# Copy_of_DAP-Peripherals-4.net
KiCad netlist of a schematic drawn in Altium Designer
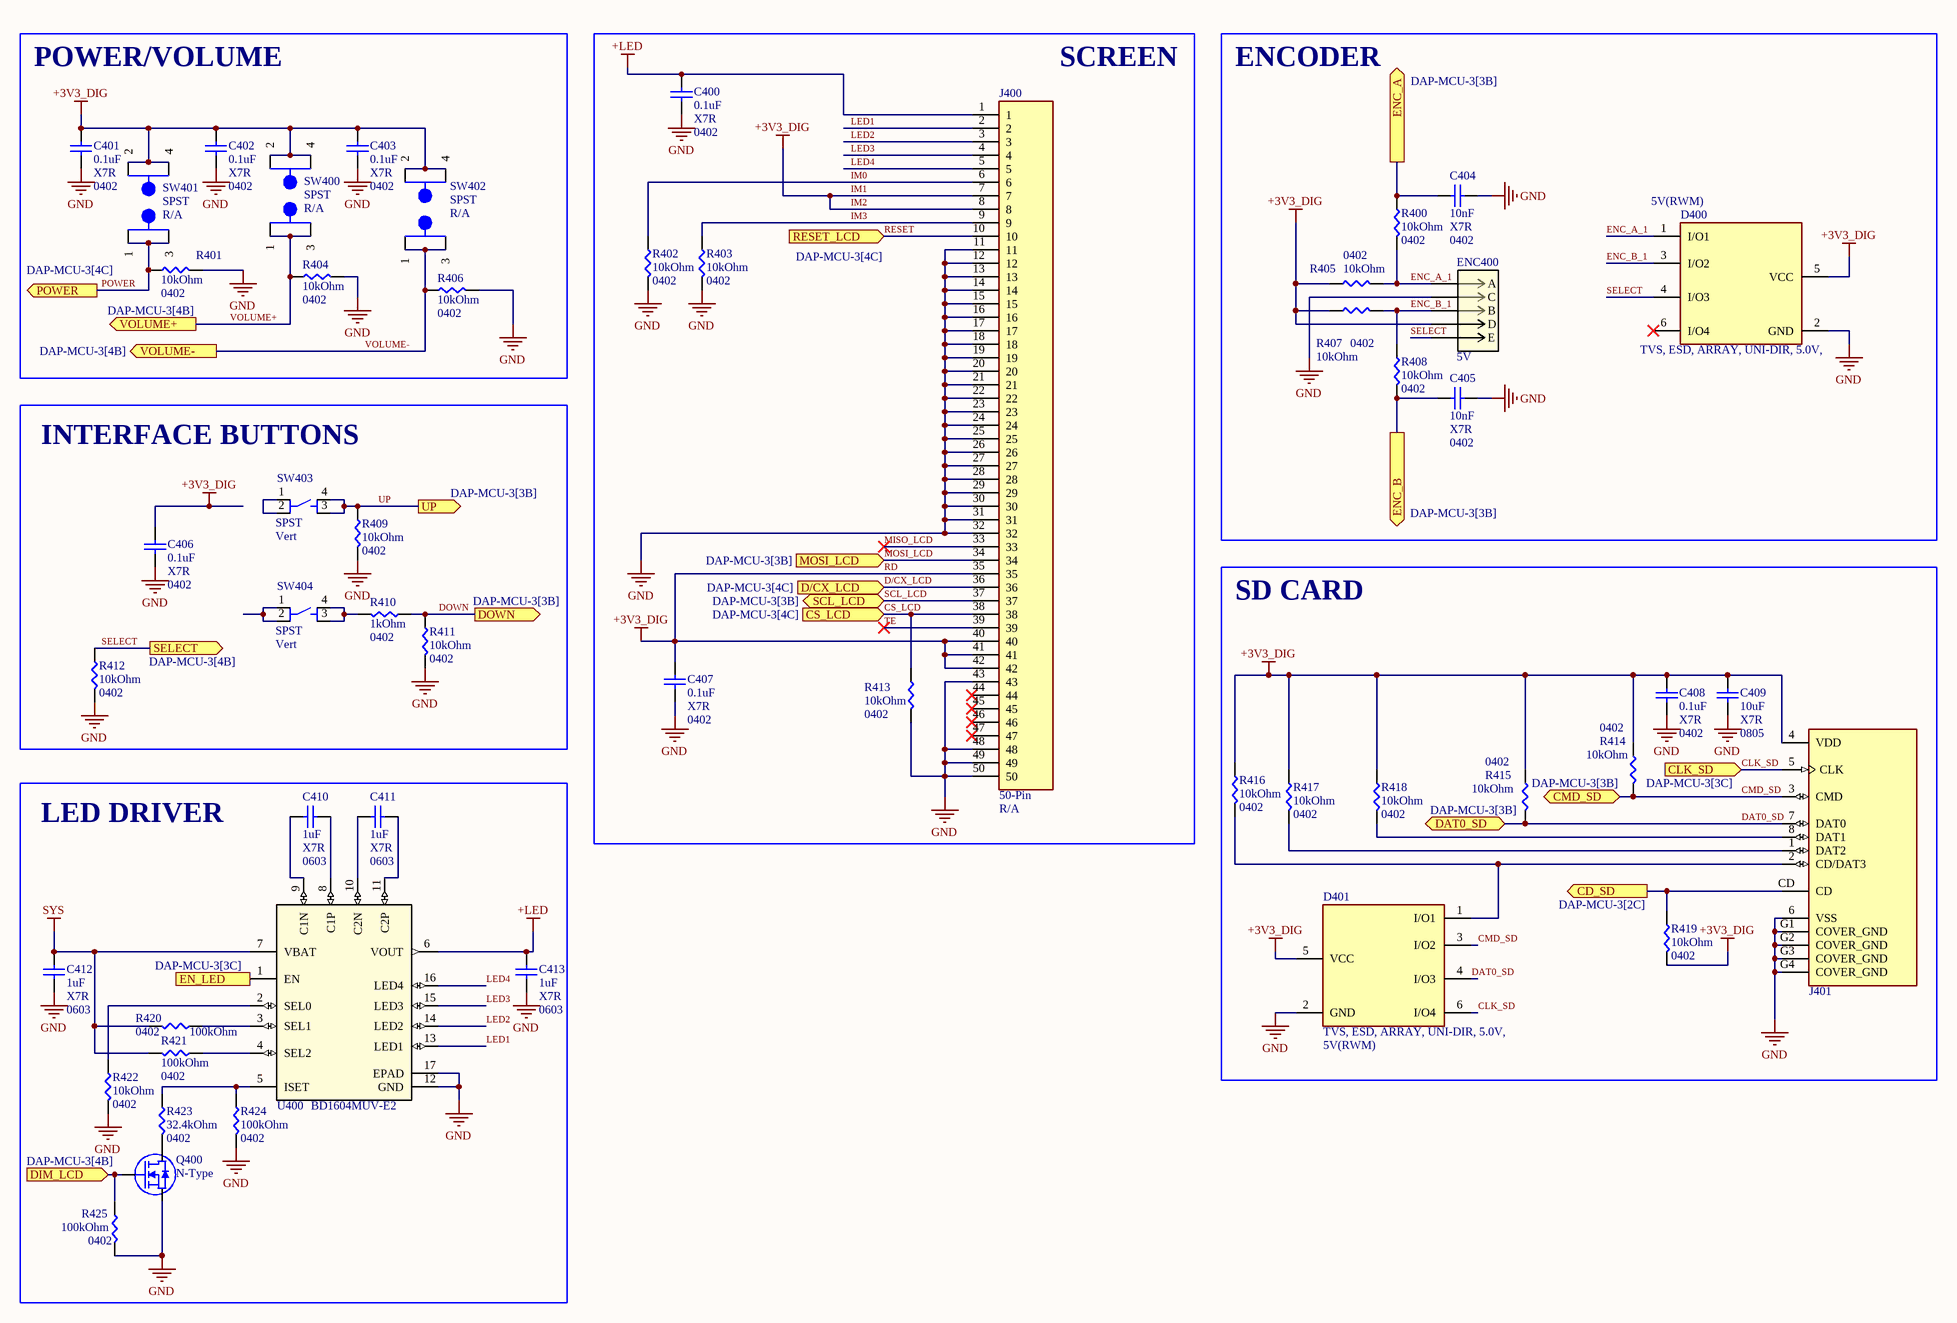
[diagram p0: Copy of DAP-Peripherals-4.SchDoc]

(export (version "E")
  (design (tool "Eeschema 10.0.6"))
  (components
    (comp (ref "C400")
      (value "CAP CER 0.1UF 50V X7R 0402")
      (footprint "CAPC1005X60N")
      (fields
        (field (name "<VALUE>") "0.1uF")
        (field (name "<SPEC>") "X7R")
        (field (name "<FOOTPRINT>") "0402")
        (field (name "CREATOR PROJECT") "DAP")
      )
      (libsource (lib "aloker-Link") (part "CAP"))
    )
    (comp (ref "C401")
      (value "CAP CER 0.1UF 50V X7R 0402")
      (footprint "CAPC1005X60N")
      (fields
        (field (name "<VALUE>") "0.1uF")
        (field (name "<SPEC>") "X7R")
        (field (name "<FOOTPRINT>") "0402")
        (field (name "CREATOR PROJECT") "DAP")
      )
      (libsource (lib "aloker-Link") (part "CAP"))
    )
    (comp (ref "C402")
      (value "CAP CER 0.1UF 50V X7R 0402")
      (footprint "CAPC1005X60N")
      (fields
        (field (name "<VALUE>") "0.1uF")
        (field (name "<SPEC>") "X7R")
        (field (name "<FOOTPRINT>") "0402")
        (field (name "CREATOR PROJECT") "DAP")
      )
      (libsource (lib "aloker-Link") (part "CAP"))
    )
    (comp (ref "C403")
      (value "CAP CER 0.1UF 50V X7R 0402")
      (footprint "CAPC1005X60N")
      (fields
        (field (name "<VALUE>") "0.1uF")
        (field (name "<SPEC>") "X7R")
        (field (name "<FOOTPRINT>") "0402")
        (field (name "CREATOR PROJECT") "DAP")
      )
      (libsource (lib "aloker-Link") (part "CAP"))
    )
    (comp (ref "C404")
      (value "CAP CER 10000PF 16V X7R 0402")
      (footprint "CAPC1005X55N")
      (fields
        (field (name "<VALUE>") "10nF")
        (field (name "<SPEC>") "X7R")
        (field (name "<FOOTPRINT>") "0402")
        (field (name "CREATOR PROJECT") "aRTy")
      )
      (libsource (lib "aloker-Link") (part "CAP"))
    )
    (comp (ref "C405")
      (value "CAP CER 10000PF 16V X7R 0402")
      (footprint "CAPC1005X55N")
      (fields
        (field (name "<VALUE>") "10nF")
        (field (name "<SPEC>") "X7R")
        (field (name "<FOOTPRINT>") "0402")
        (field (name "CREATOR PROJECT") "aRTy")
      )
      (libsource (lib "aloker-Link") (part "CAP"))
    )
    (comp (ref "C406")
      (value "CAP CER 0.1UF 50V X7R 0402")
      (footprint "CAPC1005X60N")
      (fields
        (field (name "<VALUE>") "0.1uF")
        (field (name "<SPEC>") "X7R")
        (field (name "<FOOTPRINT>") "0402")
        (field (name "CREATOR PROJECT") "DAP")
      )
      (libsource (lib "aloker-Link") (part "CAP"))
    )
    (comp (ref "C407")
      (value "CAP CER 0.1UF 50V X7R 0402")
      (footprint "CAPC1005X60N")
      (fields
        (field (name "<VALUE>") "0.1uF")
        (field (name "<SPEC>") "X7R")
        (field (name "<FOOTPRINT>") "0402")
        (field (name "CREATOR PROJECT") "DAP")
      )
      (libsource (lib "aloker-Link") (part "CAP"))
    )
    (comp (ref "C408")
      (value "CAP CER 0.1UF 50V X7R 0402")
      (footprint "CAPC1005X60N")
      (fields
        (field (name "<VALUE>") "0.1uF")
        (field (name "<SPEC>") "X7R")
        (field (name "<FOOTPRINT>") "0402")
        (field (name "CREATOR PROJECT") "DAP")
      )
      (libsource (lib "aloker-Link") (part "CAP"))
    )
    (comp (ref "C409")
      (value "CAP CER 10UF 10V X7R 0805")
      (footprint "CAPC2012X140N")
      (fields
        (field (name "<VALUE>") "10uF")
        (field (name "<SPEC>") "X7R")
        (field (name "<FOOTPRINT>") "0805")
        (field (name "CREATOR PROJECT") "DAP")
      )
      (libsource (lib "aloker-Link") (part "CAP"))
    )
    (comp (ref "C410")
      (value "CAP CER 1UF 25V X7R 0603")
      (footprint "CAPC1608X100N")
      (fields
        (field (name "<VALUE>") "1uF")
        (field (name "<SPEC>") "X7R")
        (field (name "<FOOTPRINT>") "0603")
        (field (name "CREATOR PROJECT") "DAP")
      )
      (libsource (lib "aloker-Link") (part "CAP"))
    )
    (comp (ref "C411")
      (value "CAP CER 1UF 25V X7R 0603")
      (footprint "CAPC1608X100N")
      (fields
        (field (name "<VALUE>") "1uF")
        (field (name "<SPEC>") "X7R")
        (field (name "<FOOTPRINT>") "0603")
        (field (name "CREATOR PROJECT") "DAP")
      )
      (libsource (lib "aloker-Link") (part "CAP"))
    )
    (comp (ref "C412")
      (value "CAP CER 1UF 25V X7R 0603")
      (footprint "CAPC1608X100N")
      (fields
        (field (name "<VALUE>") "1uF")
        (field (name "<SPEC>") "X7R")
        (field (name "<FOOTPRINT>") "0603")
        (field (name "CREATOR PROJECT") "DAP")
      )
      (libsource (lib "aloker-Link") (part "CAP"))
    )
    (comp (ref "C413")
      (value "CAP CER 1UF 25V X7R 0603")
      (footprint "CAPC1608X100N")
      (fields
        (field (name "<VALUE>") "1uF")
        (field (name "<SPEC>") "X7R")
        (field (name "<FOOTPRINT>") "0603")
        (field (name "CREATOR PROJECT") "DAP")
      )
      (libsource (lib "aloker-Link") (part "CAP"))
    )
    (comp (ref "D400")
      (value "TVS, ESD, ARRAY, UNI-DIR, 5.0V,")
      (footprint "TVS_ARR_4UNI_FP")
      (fields (field (name "<VALUE>") "5V(RWM)") (field (name "CREATOR PROJECT") "DAP"))
      (libsource (lib "aloker-Link") (part "TVS_ARR_4UNI"))
    )
    (comp (ref "D401")
      (value "TVS, ESD, ARRAY, UNI-DIR, 5.0V,")
      (footprint "TVS_ARR_4UNI_FP")
      (fields (field (name "<VALUE>") "5V(RWM)") (field (name "CREATOR PROJECT") "DAP"))
      (libsource (lib "") (part "TVS_ARR_4UNI_1"))
    )
    (comp (ref "ENC400")
      (value "ENCODER INCREM QUAD VERT PC PIN")
      (footprint "CONN03_EC12D1564404")
      (fields (field (name "<VALUE>") "5V") (field (name "CREATOR PROJECT") "DAP"))
      (libsource (lib "aloker-Link") (part "ENC_SWITCH"))
    )
    (comp (ref "J400")
      (value "CONN FFC BOTTOM 50POS 0.5MM R/A")
      (footprint "AMPHENOL_F32D-1A7Y1-21050")
      (fields
        (field (name "MF") "Amphenol ICC (FCI)")
        (field (name "MP") "F32D-1A7Y1-21050")
        (field (name "<VALUE>") "50-Pin")
        (field (name "<FOOTPRINT>") "R/A")
        (field (name "CREATOR PROJECT") "DAP")
      )
      (libsource (lib "aloker-Link") (part "F32D-1A7Y1-21050"))
    )
    (comp (ref "J401")
      (value "CONN MICROSD CARD R/A SMD")
      (footprint "CUI_MSD-1-A")
      (fields
        (field (name "MF") "Same Sky")
        (field (name "MP") "MSD-1-A")
        (field (name "CREATOR PROJECT") "DAP")
      )
      (libsource (lib "aloker-Link") (part "MSD-1-A"))
    )
    (comp (ref "Q400")
      (value "MOSFET N-CH 60V 115MA SOT23")
      (footprint "SOT-23_MCC")
      (fields
        (field (name "MF") "Micro Commercial")
        (field (name "MP") "2N7002-TP")
        (field (name "<VALUE>") "N-Type")
        (field (name "CREATOR PROJECT") "DAP")
      )
      (libsource (lib "aloker-Link") (part "N-MOSFET"))
    )
    (comp (ref "R400")
      (value "RES SMD 10K OHM 1% 1/16W 0402")
      (footprint "RESC1005X40N")
      (fields
        (field (name "<VALUE>") "10kOhm")
        (field (name "<FOOTPRINT>") "0402")
        (field (name "CREATOR PROJECT") "DAP")
      )
      (libsource (lib "aloker-Link") (part "RES"))
    )
    (comp (ref "R401")
      (value "RES SMD 10K OHM 1% 1/16W 0402")
      (footprint "RESC1005X40N")
      (fields
        (field (name "<VALUE>") "10kOhm")
        (field (name "<FOOTPRINT>") "0402")
        (field (name "CREATOR PROJECT") "DAP")
      )
      (libsource (lib "aloker-Link") (part "RES"))
    )
    (comp (ref "R402")
      (value "RES SMD 10K OHM 1% 1/16W 0402")
      (footprint "RESC1005X40N")
      (fields
        (field (name "<VALUE>") "10kOhm")
        (field (name "<FOOTPRINT>") "0402")
        (field (name "CREATOR PROJECT") "DAP")
      )
      (libsource (lib "aloker-Link") (part "RES"))
    )
    (comp (ref "R403")
      (value "RES SMD 10K OHM 1% 1/16W 0402")
      (footprint "RESC1005X40N")
      (fields
        (field (name "<VALUE>") "10kOhm")
        (field (name "<FOOTPRINT>") "0402")
        (field (name "CREATOR PROJECT") "DAP")
      )
      (libsource (lib "aloker-Link") (part "RES"))
    )
    (comp (ref "R404")
      (value "RES SMD 10K OHM 1% 1/16W 0402")
      (footprint "RESC1005X40N")
      (fields
        (field (name "<VALUE>") "10kOhm")
        (field (name "<FOOTPRINT>") "0402")
        (field (name "CREATOR PROJECT") "DAP")
      )
      (libsource (lib "aloker-Link") (part "RES"))
    )
    (comp (ref "R405")
      (value "RES SMD 10K OHM 1% 1/16W 0402")
      (footprint "RESC1005X40N")
      (fields
        (field (name "<VALUE>") "10kOhm")
        (field (name "<FOOTPRINT>") "0402")
        (field (name "CREATOR PROJECT") "DAP")
      )
      (libsource (lib "aloker-Link") (part "RES"))
    )
    (comp (ref "R406")
      (value "RES SMD 10K OHM 1% 1/16W 0402")
      (footprint "RESC1005X40N")
      (fields
        (field (name "<VALUE>") "10kOhm")
        (field (name "<FOOTPRINT>") "0402")
        (field (name "CREATOR PROJECT") "DAP")
      )
      (libsource (lib "aloker-Link") (part "RES"))
    )
    (comp (ref "R407")
      (value "RES SMD 10K OHM 1% 1/16W 0402")
      (footprint "RESC1005X40N")
      (fields
        (field (name "<VALUE>") "10kOhm")
        (field (name "<FOOTPRINT>") "0402")
        (field (name "CREATOR PROJECT") "DAP")
      )
      (libsource (lib "aloker-Link") (part "RES"))
    )
    (comp (ref "R408")
      (value "RES SMD 10K OHM 1% 1/16W 0402")
      (footprint "RESC1005X40N")
      (fields
        (field (name "<VALUE>") "10kOhm")
        (field (name "<FOOTPRINT>") "0402")
        (field (name "CREATOR PROJECT") "DAP")
      )
      (libsource (lib "aloker-Link") (part "RES"))
    )
    (comp (ref "R409")
      (value "RES SMD 10K OHM 1% 1/16W 0402")
      (footprint "RESC1005X40N")
      (fields
        (field (name "<VALUE>") "10kOhm")
        (field (name "<FOOTPRINT>") "0402")
        (field (name "CREATOR PROJECT") "DAP")
      )
      (libsource (lib "aloker-Link") (part "RES"))
    )
    (comp (ref "R410")
      (value "RES SMD 1K OHM 0.1% 1/16W 0402")
      (footprint "RESC1005X40N")
      (fields
        (field (name "<VALUE>") "1kOhm")
        (field (name "<FOOTPRINT>") "0402")
        (field (name "CREATOR PROJECT") "aRTy")
      )
      (libsource (lib "aloker-Link") (part "RES"))
    )
    (comp (ref "R411")
      (value "RES SMD 10K OHM 1% 1/16W 0402")
      (footprint "RESC1005X40N")
      (fields
        (field (name "<VALUE>") "10kOhm")
        (field (name "<FOOTPRINT>") "0402")
        (field (name "CREATOR PROJECT") "DAP")
      )
      (libsource (lib "aloker-Link") (part "RES"))
    )
    (comp (ref "R412")
      (value "RES SMD 10K OHM 1% 1/16W 0402")
      (footprint "RESC1005X40N")
      (fields
        (field (name "<VALUE>") "10kOhm")
        (field (name "<FOOTPRINT>") "0402")
        (field (name "CREATOR PROJECT") "DAP")
      )
      (libsource (lib "aloker-Link") (part "RES"))
    )
    (comp (ref "R413")
      (value "RES SMD 10K OHM 1% 1/16W 0402")
      (footprint "RESC1005X40N")
      (fields
        (field (name "<VALUE>") "10kOhm")
        (field (name "<FOOTPRINT>") "0402")
        (field (name "CREATOR PROJECT") "DAP")
      )
      (libsource (lib "aloker-Link") (part "RES"))
    )
    (comp (ref "R414")
      (value "RES SMD 10K OHM 1% 1/16W 0402")
      (footprint "RESC1005X40N")
      (fields
        (field (name "<VALUE>") "10kOhm")
        (field (name "<FOOTPRINT>") "0402")
        (field (name "CREATOR PROJECT") "DAP")
      )
      (libsource (lib "aloker-Link") (part "RES"))
    )
    (comp (ref "R415")
      (value "RES SMD 10K OHM 1% 1/16W 0402")
      (footprint "RESC1005X40N")
      (fields
        (field (name "<VALUE>") "10kOhm")
        (field (name "<FOOTPRINT>") "0402")
        (field (name "CREATOR PROJECT") "DAP")
      )
      (libsource (lib "aloker-Link") (part "RES"))
    )
    (comp (ref "R416")
      (value "RES SMD 10K OHM 1% 1/16W 0402")
      (footprint "RESC1005X40N")
      (fields
        (field (name "<VALUE>") "10kOhm")
        (field (name "<FOOTPRINT>") "0402")
        (field (name "CREATOR PROJECT") "DAP")
      )
      (libsource (lib "aloker-Link") (part "RES"))
    )
    (comp (ref "R417")
      (value "RES SMD 10K OHM 1% 1/16W 0402")
      (footprint "RESC1005X40N")
      (fields
        (field (name "<VALUE>") "10kOhm")
        (field (name "<FOOTPRINT>") "0402")
        (field (name "CREATOR PROJECT") "DAP")
      )
      (libsource (lib "aloker-Link") (part "RES"))
    )
    (comp (ref "R418")
      (value "RES SMD 10K OHM 1% 1/16W 0402")
      (footprint "RESC1005X40N")
      (fields
        (field (name "<VALUE>") "10kOhm")
        (field (name "<FOOTPRINT>") "0402")
        (field (name "CREATOR PROJECT") "DAP")
      )
      (libsource (lib "aloker-Link") (part "RES"))
    )
    (comp (ref "R419")
      (value "RES SMD 10K OHM 1% 1/16W 0402")
      (footprint "RESC1005X40N")
      (fields
        (field (name "<VALUE>") "10kOhm")
        (field (name "<FOOTPRINT>") "0402")
        (field (name "CREATOR PROJECT") "DAP")
      )
      (libsource (lib "aloker-Link") (part "RES"))
    )
    (comp (ref "R420")
      (value "RES SMD 100K OHM 0.1% 1/16W 0402")
      (footprint "RESC1005X40N")
      (fields
        (field (name "<VALUE>") "100kOhm")
        (field (name "<FOOTPRINT>") "0402")
        (field (name "CREATOR PROJECT") "DAP")
      )
      (libsource (lib "aloker-Link") (part "RES"))
    )
    (comp (ref "R421")
      (value "RES SMD 100K OHM 0.1% 1/16W 0402")
      (footprint "RESC1005X40N")
      (fields
        (field (name "<VALUE>") "100kOhm")
        (field (name "<FOOTPRINT>") "0402")
        (field (name "CREATOR PROJECT") "DAP")
      )
      (libsource (lib "aloker-Link") (part "RES"))
    )
    (comp (ref "R422")
      (value "RES SMD 10K OHM 1% 1/16W 0402")
      (footprint "RESC1005X40N")
      (fields
        (field (name "<VALUE>") "10kOhm")
        (field (name "<FOOTPRINT>") "0402")
        (field (name "CREATOR PROJECT") "DAP")
      )
      (libsource (lib "aloker-Link") (part "RES"))
    )
    (comp (ref "R423")
      (value "RES 32.4K OHM 1% 1/16W 0402")
      (footprint "RESC1005X40N")
      (fields
        (field (name "<VALUE>") "32.4kOhm")
        (field (name "<FOOTPRINT>") "0402")
        (field (name "CREATOR PROJECT") "DAP")
      )
      (libsource (lib "aloker-Link") (part "RES"))
    )
    (comp (ref "R424")
      (value "RES SMD 100K OHM 0.1% 1/16W 0402")
      (footprint "RESC1005X40N")
      (fields
        (field (name "<VALUE>") "100kOhm")
        (field (name "<FOOTPRINT>") "0402")
        (field (name "CREATOR PROJECT") "DAP")
      )
      (libsource (lib "aloker-Link") (part "RES"))
    )
    (comp (ref "R425")
      (value "RES SMD 100K OHM 0.1% 1/16W 0402")
      (footprint "RESC1005X40N")
      (fields
        (field (name "<VALUE>") "100kOhm")
        (field (name "<FOOTPRINT>") "0402")
        (field (name "CREATOR PROJECT") "DAP")
      )
      (libsource (lib "aloker-Link") (part "RES"))
    )
    (comp (ref "SW400")
      (value "SWITCH TACTILE SPST-NO 0.05A 12V")
      (footprint "SW_TL1014BF220QG")
      (fields
        (field (name "<VALUE>") "SPST")
        (field (name "<FOOTPRINT>") "R/A")
        (field (name "CREATOR PROJECT") "DAP")
      )
      (libsource (lib "aloker-Link") (part "SWITCH_SPST"))
    )
    (comp (ref "SW401")
      (value "SWITCH TACTILE SPST-NO 0.05A 12V")
      (footprint "SW_TL1014BF220QG")
      (fields
        (field (name "<VALUE>") "SPST")
        (field (name "<FOOTPRINT>") "R/A")
        (field (name "CREATOR PROJECT") "DAP")
      )
      (libsource (lib "aloker-Link") (part "SWITCH_SPST"))
    )
    (comp (ref "SW402")
      (value "SWITCH TACTILE SPST-NO 0.05A 12V")
      (footprint "SW_TL1014BF220QG")
      (fields
        (field (name "<VALUE>") "SPST")
        (field (name "<FOOTPRINT>") "R/A")
        (field (name "CREATOR PROJECT") "DAP")
      )
      (libsource (lib "aloker-Link") (part "SWITCH_SPST"))
    )
    (comp (ref "SW403")
      (value "SWITCH TACTILE SPST-NO 0.05A 16V")
      (footprint "SW_PTS810_SJM_250_SMTR_LFS")
      (fields
        (field (name "MF") "C&K")
        (field (name "MP") "PTS810 SJM 250 SMTR LFS")
        (field (name "<VALUE>") "SPST")
        (field (name "<FOOTPRINT>") "Vert")
        (field (name "CREATOR PROJECT") "DAP")
      )
      (libsource (lib "aloker-Link") (part "PTS810_SJM_250_SMTR_LFS"))
    )
    (comp (ref "SW404")
      (value "SWITCH TACTILE SPST-NO 0.05A 16V")
      (footprint "SW_PTS810_SJM_250_SMTR_LFS")
      (fields
        (field (name "MF") "C&K")
        (field (name "MP") "PTS810 SJM 250 SMTR LFS")
        (field (name "<VALUE>") "SPST")
        (field (name "<FOOTPRINT>") "Vert")
        (field (name "CREATOR PROJECT") "DAP")
      )
      (libsource (lib "aloker-Link") (part "PTS810_SJM_250_SMTR_LFS"))
    )
    (comp (ref "U400")
      (value "IC LED DRIVER RGLTR 30MA 16VQFN")
      (footprint "VQFN016V3030_ROM")
      (fields
        (field (name "MANUFACTURER_PART_NUMBER") "BD1604MUV-E2")
        (field (name "MANUFACTURER PART NUMBER 1") "BD1604MUV-E2")
        (field (name "COPYRIGHT") "Copyright (C) 2025 Ultra Librarian. All rights reserved.")
        (field (name "CREATOR PROJECT") "DAP")
      )
      (libsource (lib "aloker-Link") (part "BD1604MUV-E2"))
    )
  )
  (nets
    (net (code "1") (name "+3V3_DIG") (class "Default")
      (node (ref "C401") (pin "2") (pinfunction "2_2") (pintype "passive"))
      (node (ref "C402") (pin "2") (pinfunction "2_2") (pintype "passive"))
      (node (ref "C403") (pin "2") (pinfunction "2_2") (pintype "passive"))
      (node (ref "C406") (pin "2") (pinfunction "2_2") (pintype "passive"))
      (node (ref "C407") (pin "2") (pinfunction "2_2") (pintype "passive"))
      (node (ref "C408") (pin "2") (pinfunction "2_2") (pintype "passive"))
      (node (ref "C409") (pin "2") (pinfunction "2_2") (pintype "passive"))
      (node (ref "D400") (pin "5") (pinfunction "VCC_5") (pintype "passive"))
      (node (ref "D401") (pin "5") (pinfunction "VCC_5") (pintype "passive"))
      (node (ref "ENC400") (pin "4") (pinfunction "D_4") (pintype "passive"))
      (node (ref "J400") (pin "35") (pinfunction "35_35") (pintype "passive"))
      (node (ref "J400") (pin "40") (pinfunction "40_40") (pintype "passive"))
      (node (ref "J400") (pin "41") (pinfunction "41_41") (pintype "passive"))
      (node (ref "J400") (pin "42") (pinfunction "42_42") (pintype "passive"))
      (node (ref "J400") (pin "7") (pinfunction "7_7") (pintype "passive"))
      (node (ref "J400") (pin "8") (pinfunction "8_8") (pintype "passive"))
      (node (ref "J401") (pin "4") (pinfunction "VDD_4") (pintype "power_in"))
      (node (ref "R405") (pin "2") (pinfunction "2_2") (pintype "passive"))
      (node (ref "R407") (pin "2") (pinfunction "2_2") (pintype "passive"))
      (node (ref "R414") (pin "2") (pinfunction "2_2") (pintype "passive"))
      (node (ref "R415") (pin "2") (pinfunction "2_2") (pintype "passive"))
      (node (ref "R416") (pin "2") (pinfunction "2_2") (pintype "passive"))
      (node (ref "R417") (pin "2") (pinfunction "2_2") (pintype "passive"))
      (node (ref "R418") (pin "2") (pinfunction "2_2") (pintype "passive"))
      (node (ref "R419") (pin "1") (pinfunction "1_1") (pintype "passive"))
    )
    (net (code "2") (name "+LED") (class "Default")
      (node (ref "C400") (pin "2") (pinfunction "2_2") (pintype "passive"))
      (node (ref "C413") (pin "2") (pinfunction "2_2") (pintype "passive"))
      (node (ref "J400") (pin "1") (pinfunction "1_1") (pintype "passive"))
      (node (ref "U400") (pin "6") (pinfunction "VOUT_6") (pintype "output"))
    )
    (net (code "3") (name "/CD_SD") (class "Default")
      (node (ref "J401") (pin "CD") (pinfunction "CD_CD") (pintype "passive"))
      (node (ref "R419") (pin "2") (pinfunction "2_2") (pintype "passive"))
    )
    (net (code "4") (name "/CLK_SD") (class "Default")
      (node (ref "D401") (pin "6") (pinfunction "I/O4_6") (pintype "passive"))
      (node (ref "J401") (pin "5") (pinfunction "CLK_5") (pintype "input"))
    )
    (net (code "5") (name "/CMD_SD") (class "Default")
      (node (ref "D401") (pin "3") (pinfunction "I/O2_3") (pintype "passive"))
      (node (ref "J401") (pin "3") (pinfunction "CMD_3") (pintype "bidirectional"))
      (node (ref "R414") (pin "1") (pinfunction "1_1") (pintype "passive"))
    )
    (net (code "6") (name "/CS_LCD") (class "Default")
      (node (ref "J400") (pin "38") (pinfunction "38_38") (pintype "passive"))
      (node (ref "R413") (pin "2") (pinfunction "2_2") (pintype "passive"))
    )
    (net (code "7") (name "/DAT0_SD") (class "Default")
      (node (ref "D401") (pin "4") (pinfunction "I/O3_4") (pintype "passive"))
      (node (ref "J401") (pin "7") (pinfunction "DAT0_7") (pintype "bidirectional"))
      (node (ref "R415") (pin "1") (pinfunction "1_1") (pintype "passive"))
    )
    (net (code "8") (name "/DIM_LCD") (class "Default")
      (node (ref "Q400") (pin "1") (pinfunction "G_1") (pintype "passive"))
      (node (ref "R425") (pin "2") (pinfunction "2_2") (pintype "passive"))
    )
    (net (code "9") (name "/DOWN") (class "Default")
      (node (ref "R410") (pin "2") (pinfunction "2_2") (pintype "passive"))
      (node (ref "R411") (pin "2") (pinfunction "2_2") (pintype "passive"))
    )
    (net (code "10") (name "/D{slash}CX_LCD") (class "Default")
      (node (ref "J400") (pin "36") (pinfunction "36_36") (pintype "passive"))
    )
    (net (code "11") (name "/ENC_A") (class "Default")
      (node (ref "C404") (pin "2") (pinfunction "2_2") (pintype "passive"))
      (node (ref "R400") (pin "2") (pinfunction "2_2") (pintype "passive"))
    )
    (net (code "12") (name "/ENC_A_1") (class "Default")
      (node (ref "D400") (pin "1") (pinfunction "I/O1_1") (pintype "passive"))
      (node (ref "ENC400") (pin "1") (pinfunction "A_1") (pintype "passive"))
      (node (ref "R400") (pin "1") (pinfunction "1_1") (pintype "passive"))
      (node (ref "R405") (pin "1") (pinfunction "1_1") (pintype "passive"))
    )
    (net (code "13") (name "/ENC_B") (class "Default")
      (node (ref "C405") (pin "2") (pinfunction "2_2") (pintype "passive"))
      (node (ref "R408") (pin "1") (pinfunction "1_1") (pintype "passive"))
    )
    (net (code "14") (name "/ENC_B_1") (class "Default")
      (node (ref "D400") (pin "3") (pinfunction "I/O2_3") (pintype "passive"))
      (node (ref "ENC400") (pin "3") (pinfunction "B_3") (pintype "passive"))
      (node (ref "R407") (pin "1") (pinfunction "1_1") (pintype "passive"))
      (node (ref "R408") (pin "2") (pinfunction "2_2") (pintype "passive"))
    )
    (net (code "15") (name "/EN_LED") (class "Default")
      (node (ref "U400") (pin "1") (pinfunction "EN_1") (pintype "passive"))
    )
    (net (code "16") (name "/IM0") (class "Default")
      (node (ref "J400") (pin "6") (pinfunction "6_6") (pintype "passive"))
      (node (ref "R402") (pin "2") (pinfunction "2_2") (pintype "passive"))
    )
    (net (code "17") (name "/IM3") (class "Default")
      (node (ref "J400") (pin "9") (pinfunction "9_9") (pintype "passive"))
      (node (ref "R403") (pin "2") (pinfunction "2_2") (pintype "passive"))
    )
    (net (code "18") (name "/LED1") (class "Default")
      (node (ref "J400") (pin "2") (pinfunction "2_2") (pintype "passive"))
      (node (ref "U400") (pin "13") (pinfunction "LED1_13") (pintype "bidirectional"))
    )
    (net (code "19") (name "/LED2") (class "Default")
      (node (ref "J400") (pin "3") (pinfunction "3_3") (pintype "passive"))
      (node (ref "U400") (pin "14") (pinfunction "LED2_14") (pintype "bidirectional"))
    )
    (net (code "20") (name "/LED3") (class "Default")
      (node (ref "J400") (pin "4") (pinfunction "4_4") (pintype "passive"))
      (node (ref "U400") (pin "15") (pinfunction "LED3_15") (pintype "bidirectional"))
    )
    (net (code "21") (name "/LED4") (class "Default")
      (node (ref "J400") (pin "5") (pinfunction "5_5") (pintype "passive"))
      (node (ref "U400") (pin "16") (pinfunction "LED4_16") (pintype "bidirectional"))
    )
    (net (code "22") (name "/MISO_LCD") (class "Default")
      (node (ref "J400") (pin "33") (pinfunction "33_33") (pintype "passive+no_connect"))
    )
    (net (code "23") (name "/MOSI_LCD") (class "Default")
      (node (ref "J400") (pin "34") (pinfunction "34_34") (pintype "passive"))
    )
    (net (code "24") (name "/POWER") (class "Default")
      (node (ref "R401") (pin "2") (pinfunction "2_2") (pintype "passive"))
    )
    (net (code "25") (name "/RESET") (class "Default")
      (node (ref "J400") (pin "10") (pinfunction "10_10") (pintype "passive"))
    )
    (net (code "26") (name "/SCL_LCD") (class "Default")
      (node (ref "J400") (pin "37") (pinfunction "37_37") (pintype "passive"))
    )
    (net (code "27") (name "/SELECT") (class "Default")
      (node (ref "D400") (pin "4") (pinfunction "I/O3_4") (pintype "passive"))
      (node (ref "ENC400") (pin "5") (pinfunction "E_5") (pintype "passive"))
      (node (ref "R412") (pin "2") (pinfunction "2_2") (pintype "passive"))
    )
    (net (code "28") (name "/TE") (class "Default")
      (node (ref "J400") (pin "39") (pinfunction "39_39") (pintype "passive+no_connect"))
    )
    (net (code "29") (name "/UP") (class "Default")
      (node (ref "R409") (pin "2") (pinfunction "2_2") (pintype "passive"))
      (node (ref "SW403") (pin "3") (pinfunction "3_3") (pintype "passive"))
      (node (ref "SW403") (pin "4") (pinfunction "4_4") (pintype "passive"))
    )
    (net (code "30") (name "/VOLUME+") (class "Default")
      (node (ref "R404") (pin "2") (pinfunction "2_2") (pintype "passive"))
    )
    (net (code "31") (name "/VOLUME-") (class "Default")
      (node (ref "R406") (pin "2") (pinfunction "2_2") (pintype "passive"))
    )
    (net (code "32") (name "GND") (class "Default")
      (node (ref "C400") (pin "1") (pinfunction "1_1") (pintype "passive"))
      (node (ref "C401") (pin "1") (pinfunction "1_1") (pintype "passive"))
      (node (ref "C402") (pin "1") (pinfunction "1_1") (pintype "passive"))
      (node (ref "C403") (pin "1") (pinfunction "1_1") (pintype "passive"))
      (node (ref "C404") (pin "1") (pinfunction "1_1") (pintype "passive"))
      (node (ref "C405") (pin "1") (pinfunction "1_1") (pintype "passive"))
      (node (ref "C406") (pin "1") (pinfunction "1_1") (pintype "passive"))
      (node (ref "C407") (pin "1") (pinfunction "1_1") (pintype "passive"))
      (node (ref "C408") (pin "1") (pinfunction "1_1") (pintype "passive"))
      (node (ref "C409") (pin "1") (pinfunction "1_1") (pintype "passive"))
      (node (ref "C412") (pin "1") (pinfunction "1_1") (pintype "passive"))
      (node (ref "C413") (pin "1") (pinfunction "1_1") (pintype "passive"))
      (node (ref "D400") (pin "2") (pinfunction "GND_2") (pintype "passive"))
      (node (ref "D401") (pin "2") (pinfunction "GND_2") (pintype "passive"))
      (node (ref "ENC400") (pin "2") (pinfunction "C_2") (pintype "passive"))
      (node (ref "J400") (pin "11") (pinfunction "11_11") (pintype "passive"))
      (node (ref "J400") (pin "12") (pinfunction "12_12") (pintype "passive"))
      (node (ref "J400") (pin "13") (pinfunction "13_13") (pintype "passive"))
      (node (ref "J400") (pin "14") (pinfunction "14_14") (pintype "passive"))
      (node (ref "J400") (pin "15") (pinfunction "15_15") (pintype "passive"))
      (node (ref "J400") (pin "16") (pinfunction "16_16") (pintype "passive"))
      (node (ref "J400") (pin "17") (pinfunction "17_17") (pintype "passive"))
      (node (ref "J400") (pin "18") (pinfunction "18_18") (pintype "passive"))
      (node (ref "J400") (pin "19") (pinfunction "19_19") (pintype "passive"))
      (node (ref "J400") (pin "20") (pinfunction "20_20") (pintype "passive"))
      (node (ref "J400") (pin "21") (pinfunction "21_21") (pintype "passive"))
      (node (ref "J400") (pin "22") (pinfunction "22_22") (pintype "passive"))
      (node (ref "J400") (pin "23") (pinfunction "23_23") (pintype "passive"))
      (node (ref "J400") (pin "24") (pinfunction "24_24") (pintype "passive"))
      (node (ref "J400") (pin "25") (pinfunction "25_25") (pintype "passive"))
      (node (ref "J400") (pin "26") (pinfunction "26_26") (pintype "passive"))
      (node (ref "J400") (pin "27") (pinfunction "27_27") (pintype "passive"))
      (node (ref "J400") (pin "28") (pinfunction "28_28") (pintype "passive"))
      (node (ref "J400") (pin "29") (pinfunction "29_29") (pintype "passive"))
      (node (ref "J400") (pin "30") (pinfunction "30_30") (pintype "passive"))
      (node (ref "J400") (pin "31") (pinfunction "31_31") (pintype "passive"))
      (node (ref "J400") (pin "32") (pinfunction "32_32") (pintype "passive"))
      (node (ref "J400") (pin "43") (pinfunction "43_43") (pintype "passive"))
      (node (ref "J400") (pin "48") (pinfunction "48_48") (pintype "passive"))
      (node (ref "J400") (pin "49") (pinfunction "49_49") (pintype "passive"))
      (node (ref "J400") (pin "50") (pinfunction "50_50") (pintype "passive"))
      (node (ref "J401") (pin "6") (pinfunction "VSS_6") (pintype "power_in"))
      (node (ref "J401") (pin "G1") (pinfunction "COVER_GND_G1") (pintype "power_in"))
      (node (ref "J401") (pin "G2") (pinfunction "COVER_GND_G2") (pintype "power_in"))
      (node (ref "J401") (pin "G3") (pinfunction "COVER_GND_G3") (pintype "power_in"))
      (node (ref "J401") (pin "G4") (pinfunction "COVER_GND_G4") (pintype "power_in"))
      (node (ref "Q400") (pin "2") (pinfunction "S_2") (pintype "passive"))
      (node (ref "R401") (pin "1") (pinfunction "1_1") (pintype "passive"))
      (node (ref "R402") (pin "1") (pinfunction "1_1") (pintype "passive"))
      (node (ref "R403") (pin "1") (pinfunction "1_1") (pintype "passive"))
      (node (ref "R404") (pin "1") (pinfunction "1_1") (pintype "passive"))
      (node (ref "R406") (pin "1") (pinfunction "1_1") (pintype "passive"))
      (node (ref "R409") (pin "1") (pinfunction "1_1") (pintype "passive"))
      (node (ref "R411") (pin "1") (pinfunction "1_1") (pintype "passive"))
      (node (ref "R412") (pin "1") (pinfunction "1_1") (pintype "passive"))
      (node (ref "R413") (pin "1") (pinfunction "1_1") (pintype "passive"))
      (node (ref "R422") (pin "1") (pinfunction "1_1") (pintype "passive"))
      (node (ref "R424") (pin "1") (pinfunction "1_1") (pintype "passive"))
      (node (ref "R425") (pin "1") (pinfunction "1_1") (pintype "passive"))
      (node (ref "U400") (pin "12") (pinfunction "GND_12") (pintype "power_in"))
      (node (ref "U400") (pin "17") (pinfunction "EPAD_17") (pintype "passive"))
    )
    (net (code "33") (name "Net-(D401-I{slash}O1)") (class "Default")
      (node (ref "D401") (pin "1") (pinfunction "I/O1_1") (pintype "passive"))
      (node (ref "J401") (pin "2") (pinfunction "CD/DAT3_2") (pintype "bidirectional"))
      (node (ref "R416") (pin "1") (pinfunction "1_1") (pintype "passive"))
    )
    (net (code "34") (name "Net-(J401-DAT1)") (class "Default")
      (node (ref "J401") (pin "8") (pinfunction "DAT1_8") (pintype "bidirectional"))
      (node (ref "R418") (pin "1") (pinfunction "1_1") (pintype "passive"))
    )
    (net (code "35") (name "Net-(J401-DAT2)") (class "Default")
      (node (ref "J401") (pin "1") (pinfunction "DAT2_1") (pintype "bidirectional"))
      (node (ref "R417") (pin "1") (pinfunction "1_1") (pintype "passive"))
    )
    (net (code "36") (name "Net-(Q400-D)") (class "Default")
      (node (ref "Q400") (pin "3") (pinfunction "D_3") (pintype "passive"))
      (node (ref "R423") (pin "1") (pinfunction "1_1") (pintype "passive"))
    )
    (net (code "37") (name "Net-(R410-Pad1)") (class "Default")
      (node (ref "R410") (pin "1") (pinfunction "1_1") (pintype "passive"))
      (node (ref "SW404") (pin "3") (pinfunction "3_3") (pintype "passive"))
      (node (ref "SW404") (pin "4") (pinfunction "4_4") (pintype "passive"))
    )
    (net (code "38") (name "Net-(SW403-Pad1)") (class "Default")
      (node (ref "SW403") (pin "1") (pinfunction "1_1") (pintype "passive"))
      (node (ref "SW403") (pin "2") (pinfunction "2_2") (pintype "passive"))
    )
    (net (code "39") (name "Net-(SW404-Pad1)") (class "Default")
      (node (ref "SW404") (pin "1") (pinfunction "1_1") (pintype "passive"))
      (node (ref "SW404") (pin "2") (pinfunction "2_2") (pintype "passive"))
    )
    (net (code "40") (name "Net-(U400-C1N)") (class "Default")
      (node (ref "C410") (pin "2") (pinfunction "2_2") (pintype "passive"))
      (node (ref "U400") (pin "9") (pinfunction "C1N_9") (pintype "bidirectional"))
    )
    (net (code "41") (name "Net-(U400-C1P)") (class "Default")
      (node (ref "C410") (pin "1") (pinfunction "1_1") (pintype "passive"))
      (node (ref "U400") (pin "8") (pinfunction "C1P_8") (pintype "bidirectional"))
    )
    (net (code "42") (name "Net-(U400-C2N)") (class "Default")
      (node (ref "C411") (pin "2") (pinfunction "2_2") (pintype "passive"))
      (node (ref "U400") (pin "10") (pinfunction "C2N_10") (pintype "bidirectional"))
    )
    (net (code "43") (name "Net-(U400-C2P)") (class "Default")
      (node (ref "C411") (pin "1") (pinfunction "1_1") (pintype "passive"))
      (node (ref "U400") (pin "11") (pinfunction "C2P_11") (pintype "bidirectional"))
    )
    (net (code "44") (name "Net-(U400-ISET)") (class "Default")
      (node (ref "R423") (pin "2") (pinfunction "2_2") (pintype "passive"))
      (node (ref "R424") (pin "2") (pinfunction "2_2") (pintype "passive"))
      (node (ref "U400") (pin "5") (pinfunction "ISET_5") (pintype "passive"))
    )
    (net (code "45") (name "Net-(U400-SEL0)") (class "Default")
      (node (ref "R422") (pin "2") (pinfunction "2_2") (pintype "passive"))
      (node (ref "U400") (pin "2") (pinfunction "SEL0_2") (pintype "bidirectional"))
    )
    (net (code "46") (name "Net-(U400-SEL1)") (class "Default")
      (node (ref "R420") (pin "2") (pinfunction "2_2") (pintype "passive"))
      (node (ref "U400") (pin "3") (pinfunction "SEL1_3") (pintype "bidirectional"))
    )
    (net (code "47") (name "Net-(U400-SEL2)") (class "Default")
      (node (ref "R421") (pin "2") (pinfunction "2_2") (pintype "passive"))
      (node (ref "U400") (pin "4") (pinfunction "SEL2_4") (pintype "bidirectional"))
    )
    (net (code "48") (name "SYS") (class "Default")
      (node (ref "C412") (pin "2") (pinfunction "2_2") (pintype "passive"))
      (node (ref "R420") (pin "1") (pinfunction "1_1") (pintype "passive"))
      (node (ref "R421") (pin "1") (pinfunction "1_1") (pintype "passive"))
      (node (ref "U400") (pin "7") (pinfunction "VBAT_7") (pintype "passive"))
    )
    (net (code "49") (name "unconnected-(D400-I{slash}O4-Pad6)") (class "Default")
      (node (ref "D400") (pin "6") (pinfunction "I/O4_6") (pintype "passive+no_connect"))
    )
    (net (code "50") (name "unconnected-(J400-Pad44)") (class "Default")
      (node (ref "J400") (pin "44") (pinfunction "44_44") (pintype "passive+no_connect"))
    )
    (net (code "51") (name "unconnected-(J400-Pad45)") (class "Default")
      (node (ref "J400") (pin "45") (pinfunction "45_45") (pintype "passive+no_connect"))
    )
    (net (code "52") (name "unconnected-(J400-Pad46)") (class "Default")
      (node (ref "J400") (pin "46") (pinfunction "46_46") (pintype "passive+no_connect"))
    )
    (net (code "53") (name "unconnected-(J400-Pad47)") (class "Default")
      (node (ref "J400") (pin "47") (pinfunction "47_47") (pintype "passive+no_connect"))
    )
    (net (code "54") (name "unconnected-(SW400-Pad1)") (class "Default")
      (node (ref "SW400") (pin "1") (pinfunction "1_1") (pintype "passive"))
    )
    (net (code "55") (name "unconnected-(SW400-Pad2)") (class "Default")
      (node (ref "SW400") (pin "2") (pinfunction "2_2") (pintype "passive"))
    )
    (net (code "56") (name "unconnected-(SW400-Pad3)") (class "Default")
      (node (ref "SW400") (pin "3") (pinfunction "3_3") (pintype "passive"))
    )
    (net (code "57") (name "unconnected-(SW400-Pad4)") (class "Default")
      (node (ref "SW400") (pin "4") (pinfunction "4_4") (pintype "passive"))
    )
    (net (code "58") (name "unconnected-(SW401-Pad1)") (class "Default")
      (node (ref "SW401") (pin "1") (pinfunction "1_1") (pintype "passive"))
    )
    (net (code "59") (name "unconnected-(SW401-Pad2)") (class "Default")
      (node (ref "SW401") (pin "2") (pinfunction "2_2") (pintype "passive"))
    )
    (net (code "60") (name "unconnected-(SW401-Pad3)") (class "Default")
      (node (ref "SW401") (pin "3") (pinfunction "3_3") (pintype "passive"))
    )
    (net (code "61") (name "unconnected-(SW401-Pad4)") (class "Default")
      (node (ref "SW401") (pin "4") (pinfunction "4_4") (pintype "passive"))
    )
    (net (code "62") (name "unconnected-(SW402-Pad1)") (class "Default")
      (node (ref "SW402") (pin "1") (pinfunction "1_1") (pintype "passive"))
    )
    (net (code "63") (name "unconnected-(SW402-Pad2)") (class "Default")
      (node (ref "SW402") (pin "2") (pinfunction "2_2") (pintype "passive"))
    )
    (net (code "64") (name "unconnected-(SW402-Pad3)") (class "Default")
      (node (ref "SW402") (pin "3") (pinfunction "3_3") (pintype "passive"))
    )
    (net (code "65") (name "unconnected-(SW402-Pad4)") (class "Default")
      (node (ref "SW402") (pin "4") (pinfunction "4_4") (pintype "passive"))
    )
  )
)
